# highpass-filter-conditioning.net
KiCad netlist of a schematic drawn in Altium Designer
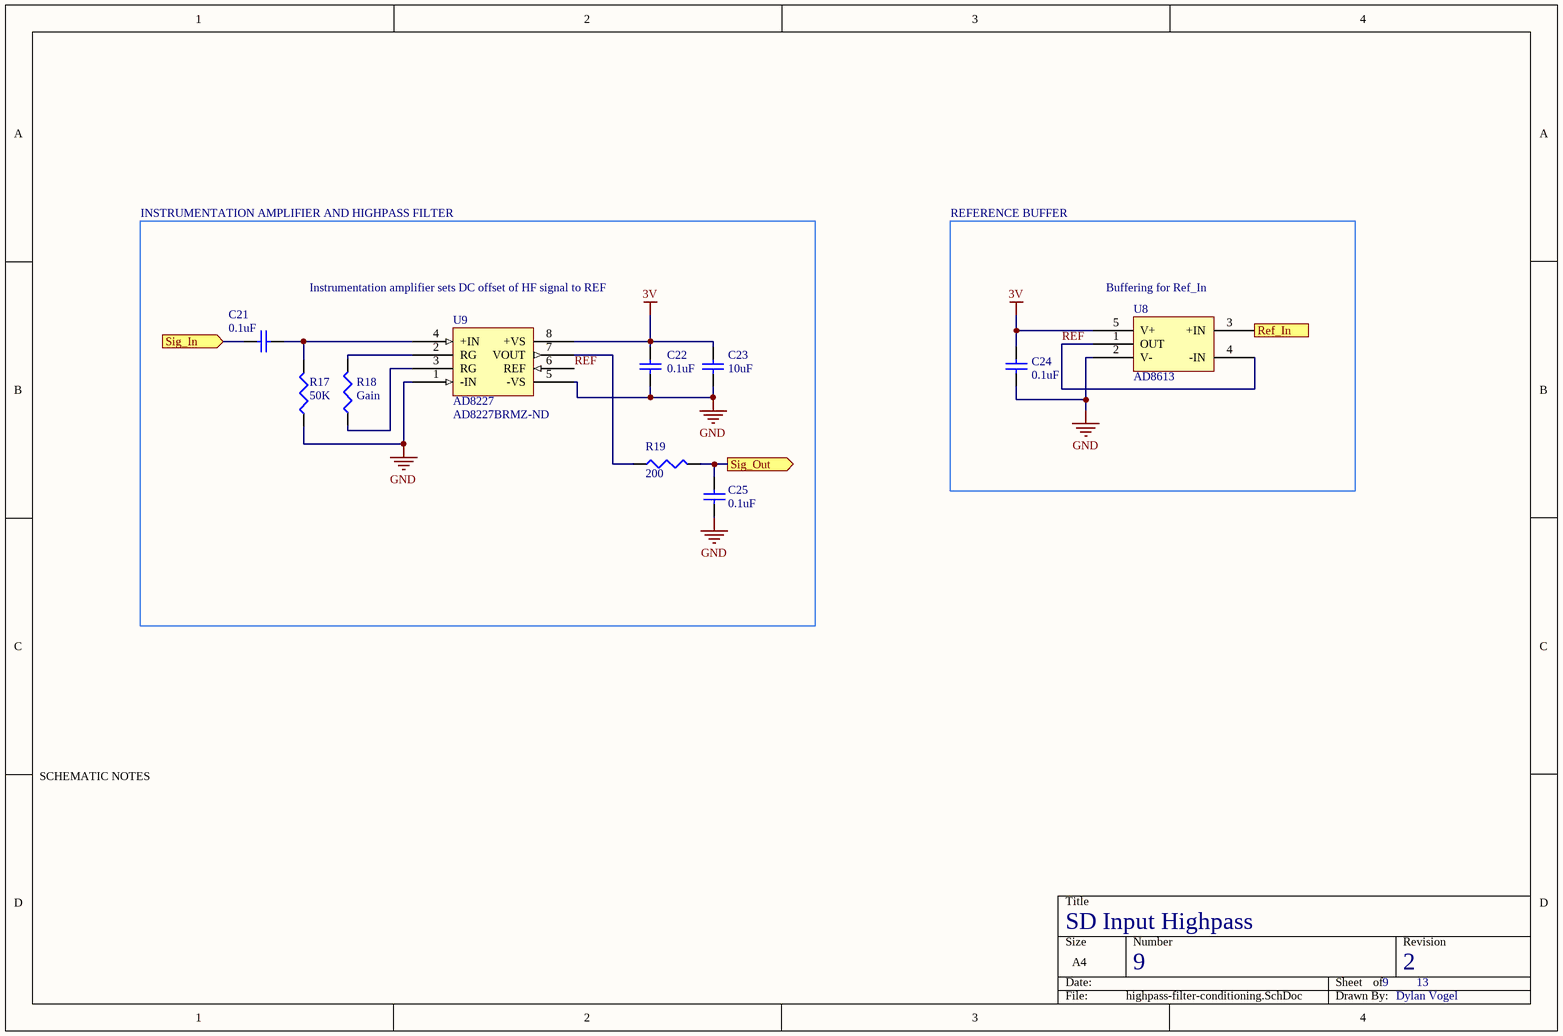
[diagram p0: highpass-filter-conditioning.SchDoc]

(export (version "E")
  (design (tool "Eeschema 10.0.6"))
  (components
    (comp (ref "C21")
      (value "0.1uF")
      (footprint "0402")
      (description "Capacitor (Semiconductor SIM Model)")
      (fields (field (name "PUBLISHER") "Altium Limited"))
      (libsource (lib "Miscellaneous Devices") (part "Cap Semi"))
    )
    (comp (ref "C22")
      (value "0.1uF")
      (footprint "0402")
      (description "Capacitor (Semiconductor SIM Model)")
      (fields (field (name "PUBLISHER") "Altium Limited"))
      (libsource (lib "Miscellaneous Devices") (part "Cap Semi"))
    )
    (comp (ref "C23")
      (value "10uF")
      (footprint "1608[0603]")
      (description "Capacitor (Semiconductor SIM Model)")
      (fields (field (name "PUBLISHER") "Altium Limited"))
      (libsource (lib "Miscellaneous Devices") (part "Cap Semi"))
    )
    (comp (ref "C24")
      (value "0.1uF")
      (footprint "0402")
      (description "Capacitor (Semiconductor SIM Model)")
      (fields (field (name "PUBLISHER") "Altium Limited"))
      (libsource (lib "Miscellaneous Devices") (part "Cap Semi"))
    )
    (comp (ref "C25")
      (value "0.1uF")
      (footprint "0402")
      (description "Capacitor (Semiconductor SIM Model)")
      (fields (field (name "PUBLISHER") "Altium Limited"))
      (libsource (lib "Miscellaneous Devices") (part "Cap Semi"))
    )
    (comp (ref "R17")
      (value "50K")
      (footprint "0402")
      (description "Resistor")
      (fields (field (name "PUBLISHER") "Altium Limited"))
      (libsource (lib "Miscellaneous Devices") (part "Res3"))
    )
    (comp (ref "R18")
      (value "Gain")
      (footprint "0402")
      (description "Optional resistor sets instrumentation amplifier gain")
      (fields (field (name "PUBLISHER") "Altium Limited"))
      (libsource (lib "Miscellaneous Devices") (part "Res3"))
    )
    (comp (ref "R19")
      (value "200")
      (footprint "0402")
      (description "Resistor")
      (fields (field (name "PUBLISHER") "Altium Limited"))
      (libsource (lib "Miscellaneous Devices") (part "Res3"))
    )
    (comp (ref "U8")
      (value "AD8613")
      (footprint "SOP-65P200X125-5N")
      (description "Low power, low noise rail-to-rail op-amp.")
      (libsource (lib "PAY") (part "AD8613"))
    )
    (comp (ref "U9")
      (value "AD8227")
      (footprint "SOP8-65P300X300-8N")
      (description "Rail-to-rail instrumentation amplifier. Can operate on single supply.")
      (fields (field (name "SUPPLIER PART NUMBER 1") "AD8227BRMZ-ND"))
      (libsource (lib "PAY") (part "AD8227"))
    )
  )
  (nets
    (net (code "1") (name "/REF") (class "Default")
      (node (ref "U8") (pin "1") (pinfunction "OUT_1") (pintype "passive"))
      (node (ref "U8") (pin "4") (pinfunction "-IN_4") (pintype "passive"))
      (node (ref "U9") (pin "6") (pinfunction "REF_6") (pintype "input"))
    )
    (net (code "2") (name "/Ref_In") (class "Default")
      (node (ref "U8") (pin "3") (pinfunction "+IN_3") (pintype "passive"))
    )
    (net (code "3") (name "/Sig_In") (class "Default")
      (node (ref "C21") (pin "2") (pinfunction "2_2") (pintype "passive"))
    )
    (net (code "4") (name "/Sig_Out") (class "Default")
      (node (ref "C25") (pin "2") (pinfunction "2_2") (pintype "passive"))
      (node (ref "R19") (pin "2") (pinfunction "2_2") (pintype "passive"))
    )
    (net (code "5") (name "3V") (class "Default")
      (node (ref "C22") (pin "2") (pinfunction "2_2") (pintype "passive"))
      (node (ref "C23") (pin "2") (pinfunction "2_2") (pintype "passive"))
      (node (ref "C24") (pin "2") (pinfunction "2_2") (pintype "passive"))
      (node (ref "U8") (pin "5") (pinfunction "V+_5") (pintype "passive"))
      (node (ref "U9") (pin "8") (pinfunction "+VS_8") (pintype "power_in"))
    )
    (net (code "6") (name "GND") (class "Default")
      (node (ref "C22") (pin "1") (pinfunction "1_1") (pintype "passive"))
      (node (ref "C23") (pin "1") (pinfunction "1_1") (pintype "passive"))
      (node (ref "C24") (pin "1") (pinfunction "1_1") (pintype "passive"))
      (node (ref "C25") (pin "1") (pinfunction "1_1") (pintype "passive"))
      (node (ref "R17") (pin "1") (pinfunction "1_1") (pintype "passive"))
      (node (ref "U8") (pin "2") (pinfunction "V-_2") (pintype "passive"))
      (node (ref "U9") (pin "1") (pinfunction "-IN_1") (pintype "input"))
      (node (ref "U9") (pin "5") (pinfunction "-VS_5") (pintype "power_in"))
    )
    (net (code "7") (name "Net-(R18-Pad1)") (class "Default")
      (node (ref "R18") (pin "1") (pinfunction "1_1") (pintype "passive"))
      (node (ref "U9") (pin "3") (pinfunction "RG_3") (pintype "passive"))
    )
    (net (code "8") (name "Net-(R18-Pad2)") (class "Default")
      (node (ref "R18") (pin "2") (pinfunction "2_2") (pintype "passive"))
      (node (ref "U9") (pin "2") (pinfunction "RG_2") (pintype "passive"))
    )
    (net (code "9") (name "Net-(U9-+IN)") (class "Default")
      (node (ref "C21") (pin "1") (pinfunction "1_1") (pintype "passive"))
      (node (ref "R17") (pin "2") (pinfunction "2_2") (pintype "passive"))
      (node (ref "U9") (pin "4") (pinfunction "+IN_4") (pintype "input"))
    )
    (net (code "10") (name "Net-(U9-VOUT)") (class "Default")
      (node (ref "R19") (pin "1") (pinfunction "1_1") (pintype "passive"))
      (node (ref "U9") (pin "7") (pinfunction "VOUT_7") (pintype "output"))
    )
  )
)
